# CAN_imp.net
KiCad netlist of a schematic drawn in EAGLE
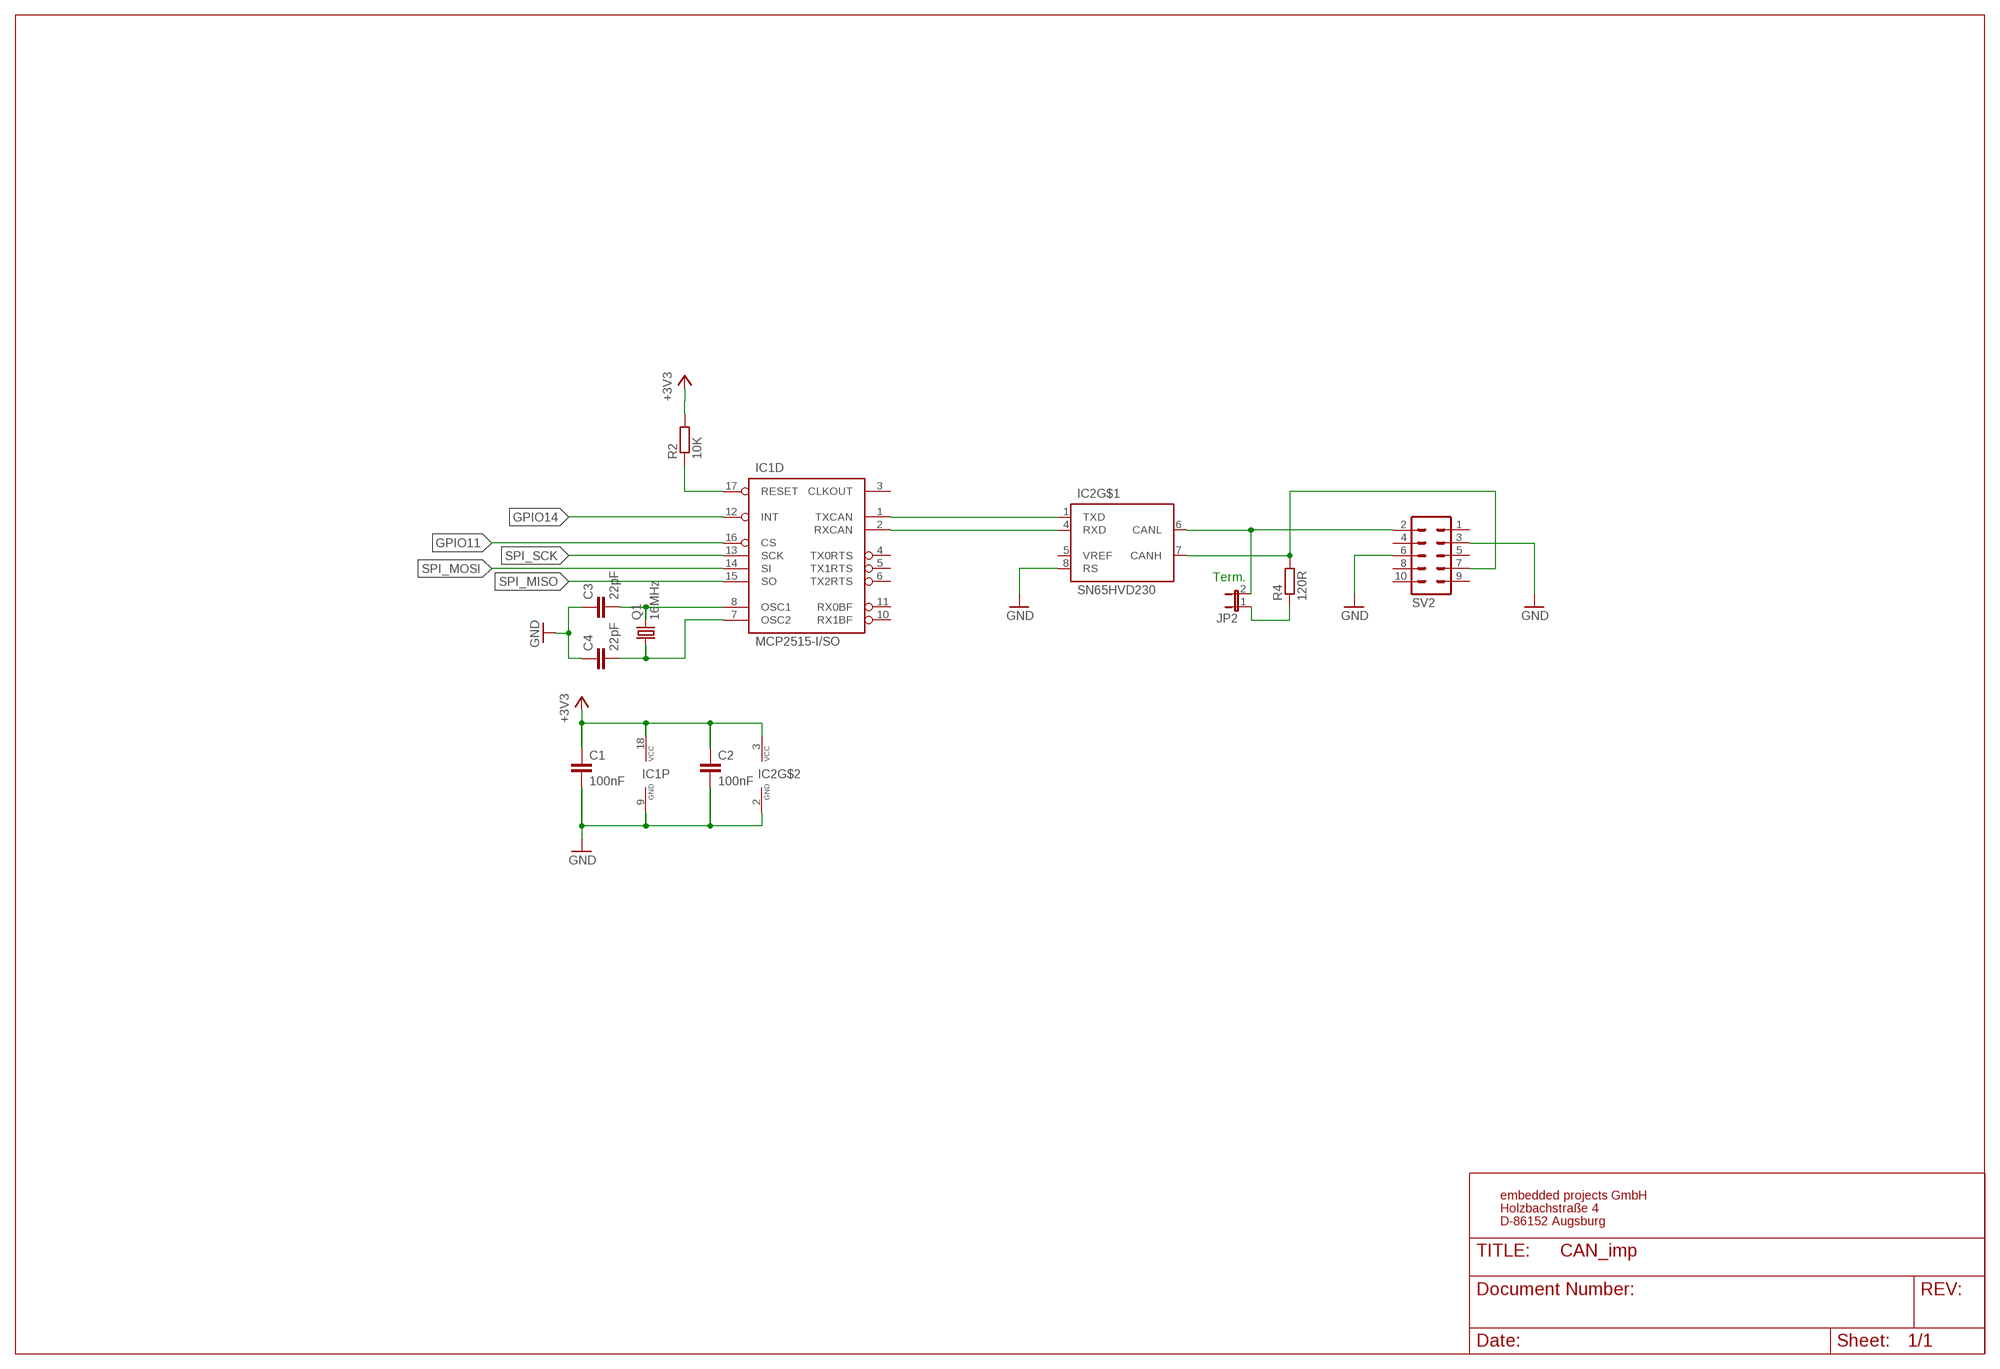
[diagram p0: schematic, sheet 1]

(export (version "E")
  (design (tool "Eeschema 10.0.6"))
  (components
    (comp (ref "C1")
      (value "100nF")
      (footprint "eagle-import:C0805")
      (libsource (lib "eagle-import") (part "C-EUC0805"))
    )
    (comp (ref "C2")
      (value "100nF")
      (footprint "eagle-import:C0805")
      (libsource (lib "eagle-import") (part "C-EUC0805"))
    )
    (comp (ref "C3")
      (value "22pF")
      (footprint "eagle-import:C0805")
      (libsource (lib "eagle-import") (part "C-EUC0805"))
    )
    (comp (ref "C4")
      (value "22pF")
      (footprint "eagle-import:C0805")
      (libsource (lib "eagle-import") (part "C-EUC0805"))
    )
    (comp (ref "IC1")
      (value "MCP2515-I/SO")
      (footprint "eagle-import:SO-18W")
      (fields (field (name "FARNELL") "1292239"))
      (libsource (lib "eagle-import") (part "MCP2515SO"))
    )
    (comp (ref "IC2")
      (value "SN65HVD230")
      (footprint "eagle-import:SO08")
      (fields (field (name "FARNELL") "1103105"))
      (libsource (lib "eagle-import") (part "MCP2551SO8"))
    )
    (comp (ref "JP2")
      (value "JP1E")
      (footprint "eagle-import:JP1")
      (libsource (lib "eagle-import") (part "JP1E"))
    )
    (comp (ref "Q1")
      (value "16MHz")
      (footprint "eagle-import:HC49UP")
      (libsource (lib "eagle-import") (part "CRYSTALHC49UP"))
    )
    (comp (ref "R2")
      (value "10K")
      (footprint "eagle-import:R0805")
      (libsource (lib "eagle-import") (part "R-EU_R0805"))
    )
    (comp (ref "R4")
      (value "120R")
      (footprint "eagle-import:R0805")
      (libsource (lib "eagle-import") (part "R-EU_R0805"))
    )
    (comp (ref "SV2")
      (value "ML10")
      (footprint "eagle-import:ML10")
      (libsource (lib "eagle-import") (part "ML10"))
    )
  )
  (nets
    (net (code "1") (name "+3V3") (class "Default")
      (node (ref "C1") (pin "1") (pinfunction "1_1") (pintype "passive"))
      (node (ref "C2") (pin "1") (pinfunction "1_1") (pintype "passive"))
      (node (ref "IC1") (pin "18") (pinfunction "VCC_18") (pintype "power_in"))
      (node (ref "IC2") (pin "3") (pinfunction "VCC_3") (pintype "power_in"))
      (node (ref "R2") (pin "2") (pinfunction "2_2") (pintype "passive"))
    )
    (net (code "2") (name "GND") (class "Default")
      (node (ref "C1") (pin "2") (pinfunction "2_2") (pintype "passive"))
      (node (ref "C2") (pin "2") (pinfunction "2_2") (pintype "passive"))
      (node (ref "C3") (pin "1") (pinfunction "1_1") (pintype "passive"))
      (node (ref "C4") (pin "1") (pinfunction "1_1") (pintype "passive"))
      (node (ref "IC1") (pin "9") (pinfunction "GND_9") (pintype "power_in"))
      (node (ref "IC2") (pin "2") (pinfunction "GND_2") (pintype "power_in"))
      (node (ref "IC2") (pin "8") (pinfunction "RS_8") (pintype "bidirectional"))
      (node (ref "SV2") (pin "3") (pinfunction "3_3") (pintype "passive"))
      (node (ref "SV2") (pin "6") (pinfunction "6_6") (pintype "passive"))
    )
    (net (code "3") (name "GPIO11") (class "Default")
      (node (ref "IC1") (pin "16") (pinfunction "CS_16") (pintype "input"))
    )
    (net (code "4") (name "GPIO14") (class "Default")
      (node (ref "IC1") (pin "12") (pinfunction "INT_12") (pintype "output"))
    )
    (net (code "5") (name "Net-(IC1A-OSC1)") (class "Default")
      (node (ref "C3") (pin "2") (pinfunction "2_2") (pintype "passive"))
      (node (ref "IC1") (pin "8") (pinfunction "OSC1_8") (pintype "input"))
      (node (ref "Q1") (pin "2") (pinfunction "2_2") (pintype "passive"))
    )
    (net (code "6") (name "Net-(IC1A-OSC2)") (class "Default")
      (node (ref "C4") (pin "2") (pinfunction "2_2") (pintype "passive"))
      (node (ref "IC1") (pin "7") (pinfunction "OSC2_7") (pintype "input"))
      (node (ref "Q1") (pin "1") (pinfunction "1_1") (pintype "passive"))
    )
    (net (code "7") (name "Net-(IC1A-RESET)") (class "Default")
      (node (ref "IC1") (pin "17") (pinfunction "RESET_17") (pintype "input"))
      (node (ref "R2") (pin "1") (pinfunction "1_1") (pintype "passive"))
    )
    (net (code "8") (name "Net-(IC1A-RXCAN)") (class "Default")
      (node (ref "IC1") (pin "2") (pinfunction "RXCAN_2") (pintype "input"))
      (node (ref "IC2") (pin "4") (pinfunction "RXD_4") (pintype "bidirectional"))
    )
    (net (code "9") (name "Net-(IC1A-TXCAN)") (class "Default")
      (node (ref "IC1") (pin "1") (pinfunction "TXCAN_1") (pintype "output"))
      (node (ref "IC2") (pin "1") (pinfunction "TXD_1") (pintype "bidirectional"))
    )
    (net (code "10") (name "Net-(IC2A-CANH)") (class "Default")
      (node (ref "IC2") (pin "7") (pinfunction "CANH_7") (pintype "bidirectional"))
      (node (ref "R4") (pin "2") (pinfunction "2_2") (pintype "passive"))
      (node (ref "SV2") (pin "7") (pinfunction "7_7") (pintype "passive"))
    )
    (net (code "11") (name "Net-(IC2A-CANL)") (class "Default")
      (node (ref "IC2") (pin "6") (pinfunction "CANL_6") (pintype "bidirectional"))
      (node (ref "JP2") (pin "2") (pinfunction "2_2") (pintype "passive"))
      (node (ref "SV2") (pin "2") (pinfunction "2_2") (pintype "passive"))
    )
    (net (code "12") (name "Net-(JP2-Pad1)") (class "Default")
      (node (ref "JP2") (pin "1") (pinfunction "1_1") (pintype "passive"))
      (node (ref "R4") (pin "1") (pinfunction "1_1") (pintype "passive"))
    )
    (net (code "13") (name "SPI_MISO") (class "Default")
      (node (ref "IC1") (pin "15") (pinfunction "SO_15") (pintype "output"))
    )
    (net (code "14") (name "SPI_MOSI") (class "Default")
      (node (ref "IC1") (pin "14") (pinfunction "SI_14") (pintype "input"))
    )
    (net (code "15") (name "SPI_SCK") (class "Default")
      (node (ref "IC1") (pin "13") (pinfunction "SCK_13") (pintype "input"))
    )
    (net (code "16") (name "unconnected-(IC1A-CLKOUT-Pad3)") (class "Default")
      (node (ref "IC1") (pin "3") (pinfunction "CLKOUT_3") (pintype "output"))
    )
    (net (code "17") (name "unconnected-(IC1A-RX0BF-Pad11)") (class "Default")
      (node (ref "IC1") (pin "11") (pinfunction "RX0BF_11") (pintype "output"))
    )
    (net (code "18") (name "unconnected-(IC1A-RX1BF-Pad10)") (class "Default")
      (node (ref "IC1") (pin "10") (pinfunction "RX1BF_10") (pintype "output"))
    )
    (net (code "19") (name "unconnected-(IC1A-TX0RTS-Pad4)") (class "Default")
      (node (ref "IC1") (pin "4") (pinfunction "TX0RTS_4") (pintype "input"))
    )
    (net (code "20") (name "unconnected-(IC1A-TX1RTS-Pad5)") (class "Default")
      (node (ref "IC1") (pin "5") (pinfunction "TX1RTS_5") (pintype "input"))
    )
    (net (code "21") (name "unconnected-(IC1A-TX2RTS-Pad6)") (class "Default")
      (node (ref "IC1") (pin "6") (pinfunction "TX2RTS_6") (pintype "input"))
    )
    (net (code "22") (name "unconnected-(IC2A-VREF-Pad5)") (class "Default")
      (node (ref "IC2") (pin "5") (pinfunction "VREF_5") (pintype "bidirectional"))
    )
    (net (code "23") (name "unconnected-(SV2-Pad1)") (class "Default")
      (node (ref "SV2") (pin "1") (pinfunction "1_1") (pintype "passive"))
    )
    (net (code "24") (name "unconnected-(SV2-Pad4)") (class "Default")
      (node (ref "SV2") (pin "4") (pinfunction "4_4") (pintype "passive"))
    )
    (net (code "25") (name "unconnected-(SV2-Pad5)") (class "Default")
      (node (ref "SV2") (pin "5") (pinfunction "5_5") (pintype "passive"))
    )
    (net (code "26") (name "unconnected-(SV2-Pad8)") (class "Default")
      (node (ref "SV2") (pin "8") (pinfunction "8_8") (pintype "passive"))
    )
    (net (code "27") (name "unconnected-(SV2-Pad9)") (class "Default")
      (node (ref "SV2") (pin "9") (pinfunction "9_9") (pintype "passive"))
    )
    (net (code "28") (name "unconnected-(SV2-Pad10)") (class "Default")
      (node (ref "SV2") (pin "10") (pinfunction "10_10") (pintype "passive"))
    )
  )
)
